# sockets.net
KiCad netlist of a schematic drawn in EAGLE
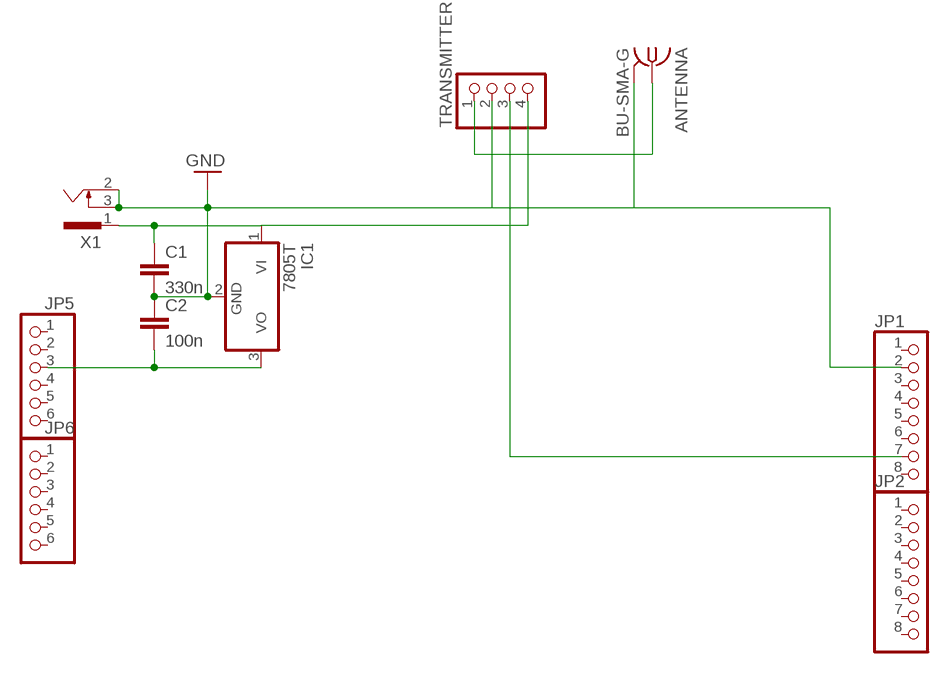
[diagram p0: schematic, sheet 1]

(export (version "E")
  (design (tool "Eeschema 10.0.6"))
  (components
    (comp (ref "ANTENNA")
      (value "BU-SMA-G")
      (footprint "eagle-import:BU-SMA-G")
      (libsource (lib "eagle-import") (part "BU-SMA-G"))
    )
    (comp (ref "C1")
      (value "330n")
      (footprint "eagle-import:C5B2.5")
      (libsource (lib "eagle-import") (part "C5/2.5"))
    )
    (comp (ref "C2")
      (value "100n")
      (footprint "eagle-import:C025-050X050")
      (libsource (lib "eagle-import") (part "C-EU025-050X050"))
    )
    (comp (ref "IC1")
      (value "7805T")
      (footprint "eagle-import:TO220H")
      (libsource (lib "eagle-import") (part "78T05"))
    )
    (comp (ref "JP1")
      (value "PINHD-1X8")
      (footprint "eagle-import:1X08")
      (libsource (lib "eagle-import") (part "PINHD-1X8"))
    )
    (comp (ref "JP2")
      (value "PINHD-1X8")
      (footprint "eagle-import:1X08")
      (libsource (lib "eagle-import") (part "PINHD-1X8"))
    )
    (comp (ref "JP5")
      (value "PINHD-1X6")
      (footprint "eagle-import:1X06")
      (libsource (lib "eagle-import") (part "PINHD-1X6"))
    )
    (comp (ref "JP6")
      (value "PINHD-1X6")
      (footprint "eagle-import:1X06")
      (libsource (lib "eagle-import") (part "PINHD-1X6"))
    )
    (comp (ref "TRANSMITTER")
      (value "PINHD-1X4")
      (footprint "eagle-import:1X04")
      (libsource (lib "eagle-import") (part "PINHD-1X4"))
    )
    (comp (ref "X1")
      (value "733980-62")
      (footprint "eagle-import:733980-62")
      (libsource (lib "eagle-import") (part "73398?0-62"))
    )
  )
  (nets
    (net (code "1") (name "GND") (class "Default")
      (node (ref "ANTENNA") (pin "2") (pinfunction "2_2") (pintype "passive"))
      (node (ref "ANTENNA") (pin "3") (pinfunction "2_3") (pintype "passive"))
      (node (ref "ANTENNA") (pin "4") (pinfunction "2_4") (pintype "passive"))
      (node (ref "ANTENNA") (pin "5") (pinfunction "2_5") (pintype "passive"))
      (node (ref "C1") (pin "2") (pinfunction "2_2") (pintype "passive"))
      (node (ref "C2") (pin "1") (pinfunction "1_1") (pintype "passive"))
      (node (ref "IC1") (pin "2") (pinfunction "GND_2") (pintype "passive"))
      (node (ref "JP1") (pin "2") (pinfunction "2_2") (pintype "passive"))
      (node (ref "TRANSMITTER") (pin "2") (pinfunction "2_2") (pintype "passive"))
      (node (ref "X1") (pin "2") (pinfunction "2_2") (pintype "passive"))
      (node (ref "X1") (pin "3") (pinfunction "3_3") (pintype "passive"))
    )
    (net (code "2") (name "Net-(ANTENNA-Pad1)") (class "Default")
      (node (ref "ANTENNA") (pin "1") (pinfunction "1_1") (pintype "passive"))
      (node (ref "TRANSMITTER") (pin "1") (pinfunction "1_1") (pintype "passive"))
    )
    (net (code "3") (name "Net-(IC1-VI)") (class "Default")
      (node (ref "C1") (pin "1") (pinfunction "1_1") (pintype "passive"))
      (node (ref "IC1") (pin "1") (pinfunction "VI_1") (pintype "input"))
      (node (ref "TRANSMITTER") (pin "4") (pinfunction "4_4") (pintype "passive"))
      (node (ref "X1") (pin "1") (pinfunction "1_1") (pintype "passive"))
    )
    (net (code "4") (name "Net-(IC1-VO)") (class "Default")
      (node (ref "C2") (pin "2") (pinfunction "2_2") (pintype "passive"))
      (node (ref "IC1") (pin "3") (pinfunction "VO_3") (pintype "passive"))
      (node (ref "JP5") (pin "3") (pinfunction "3_3") (pintype "passive"))
    )
    (net (code "5") (name "Net-(JP1-Pad7)") (class "Default")
      (node (ref "JP1") (pin "7") (pinfunction "7_7") (pintype "passive"))
      (node (ref "TRANSMITTER") (pin "3") (pinfunction "3_3") (pintype "passive"))
    )
    (net (code "6") (name "unconnected-(JP1-Pad1)") (class "Default")
      (node (ref "JP1") (pin "1") (pinfunction "1_1") (pintype "passive"))
    )
    (net (code "7") (name "unconnected-(JP1-Pad3)") (class "Default")
      (node (ref "JP1") (pin "3") (pinfunction "3_3") (pintype "passive"))
    )
    (net (code "8") (name "unconnected-(JP1-Pad4)") (class "Default")
      (node (ref "JP1") (pin "4") (pinfunction "4_4") (pintype "passive"))
    )
    (net (code "9") (name "unconnected-(JP1-Pad5)") (class "Default")
      (node (ref "JP1") (pin "5") (pinfunction "5_5") (pintype "passive"))
    )
    (net (code "10") (name "unconnected-(JP1-Pad6)") (class "Default")
      (node (ref "JP1") (pin "6") (pinfunction "6_6") (pintype "passive"))
    )
    (net (code "11") (name "unconnected-(JP1-Pad8)") (class "Default")
      (node (ref "JP1") (pin "8") (pinfunction "8_8") (pintype "passive"))
    )
    (net (code "12") (name "unconnected-(JP2-Pad1)") (class "Default")
      (node (ref "JP2") (pin "1") (pinfunction "1_1") (pintype "passive"))
    )
    (net (code "13") (name "unconnected-(JP2-Pad2)") (class "Default")
      (node (ref "JP2") (pin "2") (pinfunction "2_2") (pintype "passive"))
    )
    (net (code "14") (name "unconnected-(JP2-Pad3)") (class "Default")
      (node (ref "JP2") (pin "3") (pinfunction "3_3") (pintype "passive"))
    )
    (net (code "15") (name "unconnected-(JP2-Pad4)") (class "Default")
      (node (ref "JP2") (pin "4") (pinfunction "4_4") (pintype "passive"))
    )
    (net (code "16") (name "unconnected-(JP2-Pad5)") (class "Default")
      (node (ref "JP2") (pin "5") (pinfunction "5_5") (pintype "passive"))
    )
    (net (code "17") (name "unconnected-(JP2-Pad6)") (class "Default")
      (node (ref "JP2") (pin "6") (pinfunction "6_6") (pintype "passive"))
    )
    (net (code "18") (name "unconnected-(JP2-Pad7)") (class "Default")
      (node (ref "JP2") (pin "7") (pinfunction "7_7") (pintype "passive"))
    )
    (net (code "19") (name "unconnected-(JP2-Pad8)") (class "Default")
      (node (ref "JP2") (pin "8") (pinfunction "8_8") (pintype "passive"))
    )
    (net (code "20") (name "unconnected-(JP5-Pad1)") (class "Default")
      (node (ref "JP5") (pin "1") (pinfunction "1_1") (pintype "passive"))
    )
    (net (code "21") (name "unconnected-(JP5-Pad2)") (class "Default")
      (node (ref "JP5") (pin "2") (pinfunction "2_2") (pintype "passive"))
    )
    (net (code "22") (name "unconnected-(JP5-Pad4)") (class "Default")
      (node (ref "JP5") (pin "4") (pinfunction "4_4") (pintype "passive"))
    )
    (net (code "23") (name "unconnected-(JP5-Pad5)") (class "Default")
      (node (ref "JP5") (pin "5") (pinfunction "5_5") (pintype "passive"))
    )
    (net (code "24") (name "unconnected-(JP5-Pad6)") (class "Default")
      (node (ref "JP5") (pin "6") (pinfunction "6_6") (pintype "passive"))
    )
    (net (code "25") (name "unconnected-(JP6-Pad1)") (class "Default")
      (node (ref "JP6") (pin "1") (pinfunction "1_1") (pintype "passive"))
    )
    (net (code "26") (name "unconnected-(JP6-Pad2)") (class "Default")
      (node (ref "JP6") (pin "2") (pinfunction "2_2") (pintype "passive"))
    )
    (net (code "27") (name "unconnected-(JP6-Pad3)") (class "Default")
      (node (ref "JP6") (pin "3") (pinfunction "3_3") (pintype "passive"))
    )
    (net (code "28") (name "unconnected-(JP6-Pad4)") (class "Default")
      (node (ref "JP6") (pin "4") (pinfunction "4_4") (pintype "passive"))
    )
    (net (code "29") (name "unconnected-(JP6-Pad5)") (class "Default")
      (node (ref "JP6") (pin "5") (pinfunction "5_5") (pintype "passive"))
    )
    (net (code "30") (name "unconnected-(JP6-Pad6)") (class "Default")
      (node (ref "JP6") (pin "6") (pinfunction "6_6") (pintype "passive"))
    )
  )
)
